# KittyEarsV2.net
KiCad netlist of a schematic drawn in EAGLE
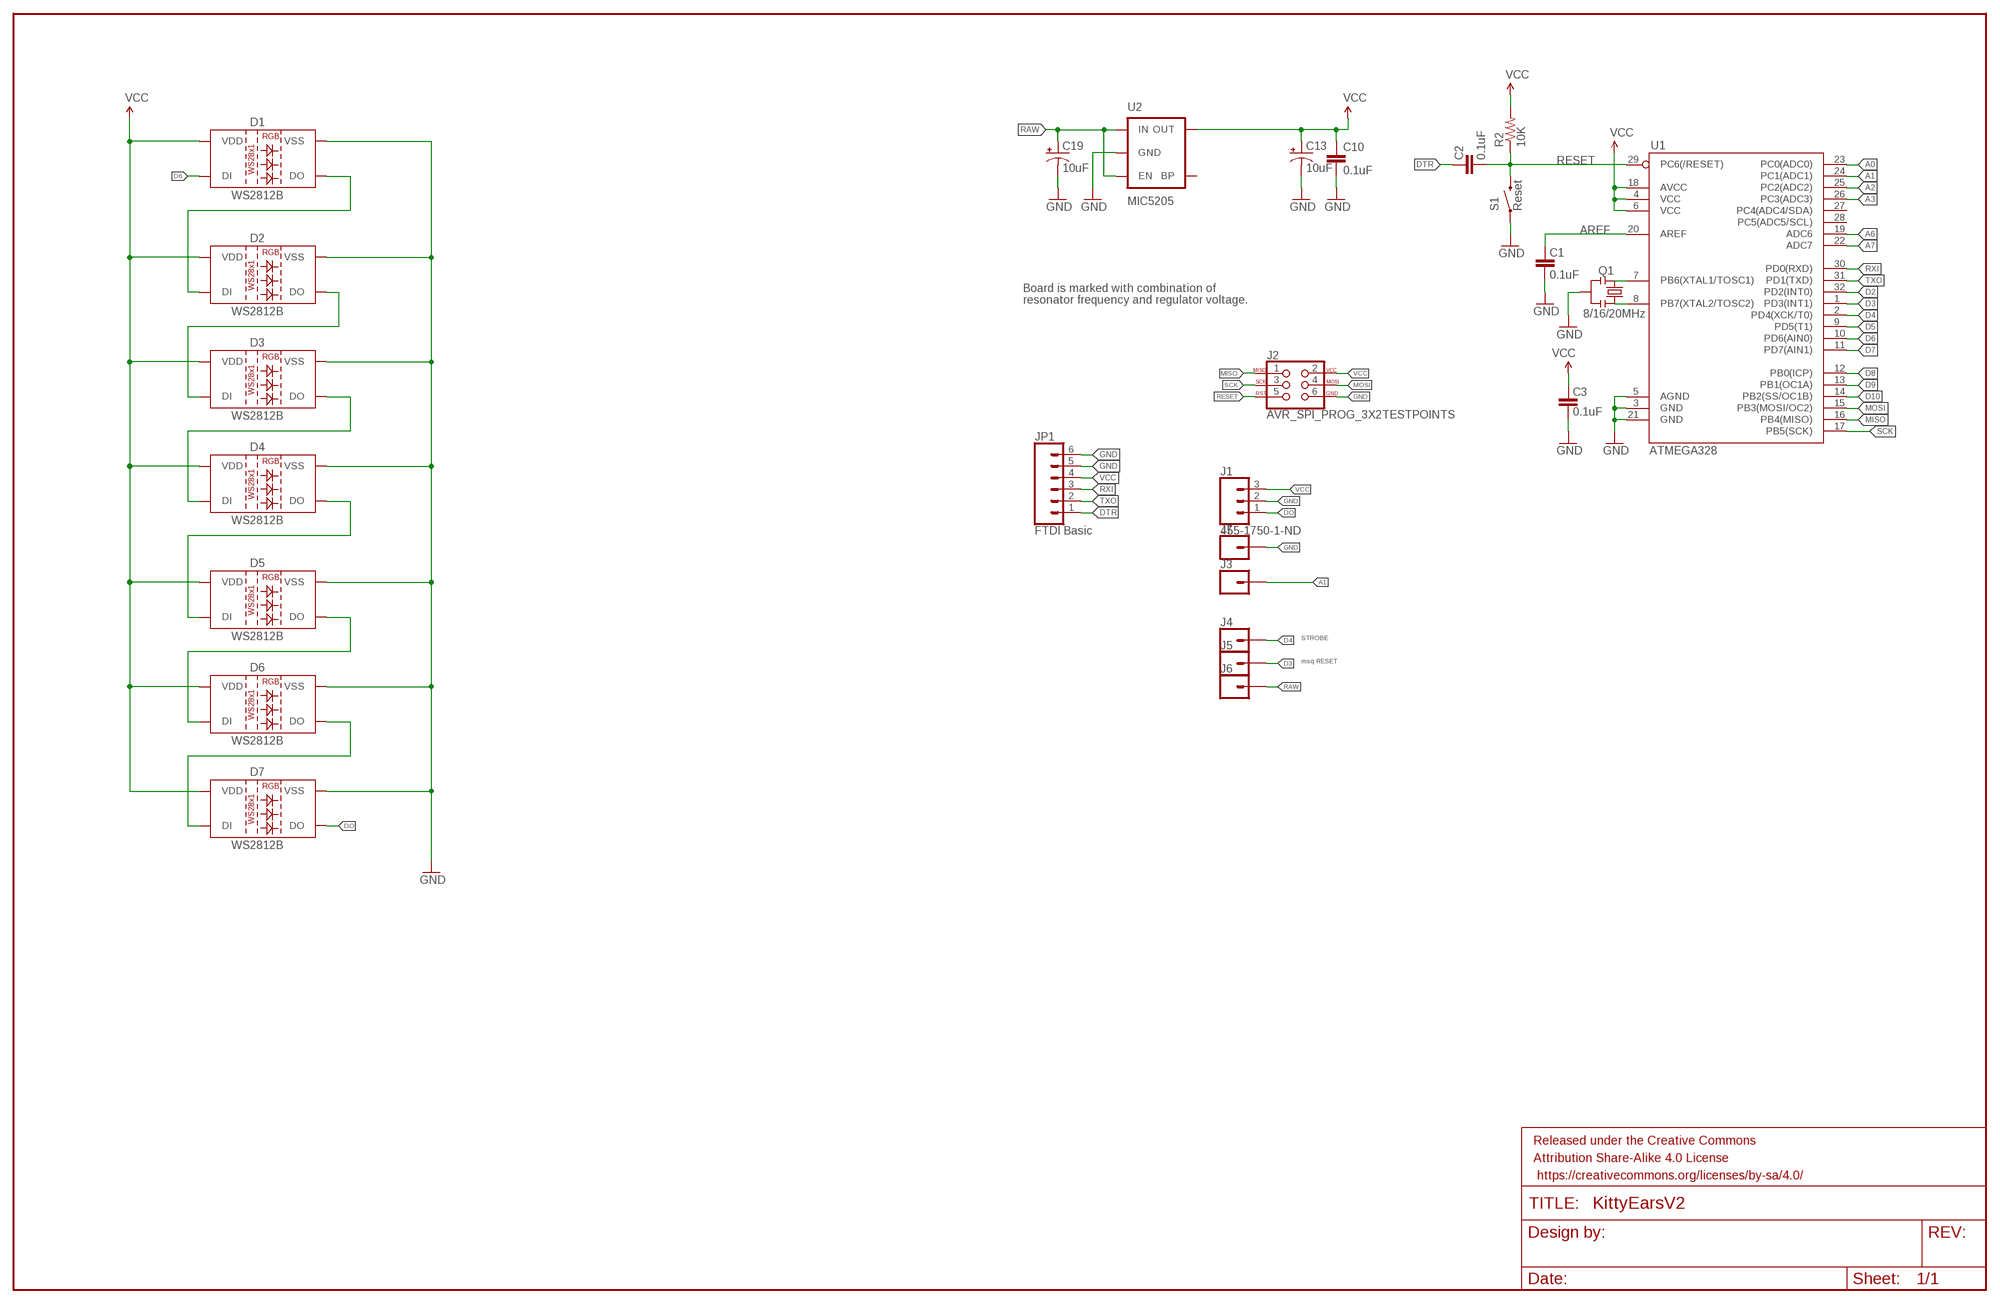
[diagram p0: schematic, sheet 1]

(export (version "E")
  (design (tool "Eeschema 10.0.6"))
  (components
    (comp (ref "C1")
      (value "0.1uF")
      (footprint "eagle-import:0603-CAP")
      (libsource (lib "eagle-import") (part "CAP0603-CAP"))
    )
    (comp (ref "C2")
      (value "0.1uF")
      (footprint "eagle-import:0603-CAP")
      (libsource (lib "eagle-import") (part "CAP0603-CAP"))
    )
    (comp (ref "C3")
      (value "0.1uF")
      (footprint "eagle-import:0603-CAP")
      (libsource (lib "eagle-import") (part "CAP0603-CAP"))
    )
    (comp (ref "C10")
      (value "0.1uF")
      (footprint "eagle-import:0603-CAP")
      (libsource (lib "eagle-import") (part "CAP0603-CAP"))
    )
    (comp (ref "C13")
      (value "10uF")
      (footprint "eagle-import:EIA3216")
      (libsource (lib "eagle-import") (part "CAP_POL1206"))
    )
    (comp (ref "C19")
      (value "10uF")
      (footprint "eagle-import:EIA3216")
      (libsource (lib "eagle-import") (part "CAP_POL1206"))
    )
    (comp (ref "D1")
      (value "WS2812B")
      (footprint "eagle-import:WS2812B")
      (libsource (lib "eagle-import") (part "WS2812B"))
    )
    (comp (ref "D2")
      (value "WS2812B")
      (footprint "eagle-import:WS2812B")
      (libsource (lib "eagle-import") (part "WS2812B"))
    )
    (comp (ref "D3")
      (value "WS2812B")
      (footprint "eagle-import:WS2812B")
      (libsource (lib "eagle-import") (part "WS2812B"))
    )
    (comp (ref "D4")
      (value "WS2812B")
      (footprint "eagle-import:WS2812B")
      (libsource (lib "eagle-import") (part "WS2812B"))
    )
    (comp (ref "D5")
      (value "WS2812B")
      (footprint "eagle-import:WS2812B")
      (libsource (lib "eagle-import") (part "WS2812B"))
    )
    (comp (ref "D6")
      (value "WS2812B")
      (footprint "eagle-import:WS2812B")
      (libsource (lib "eagle-import") (part "WS2812B"))
    )
    (comp (ref "D7")
      (value "WS2812B")
      (footprint "eagle-import:WS2812B")
      (libsource (lib "eagle-import") (part "WS2812B"))
    )
    (comp (ref "FRAME1")
      (value "FRAME-LEDGER")
      (footprint "eagle-import:CREATIVE_COMMONS")
      (libsource (lib "eagle-import") (part "FRAME-LEDGER"))
    )
    (comp (ref "J1")
      (value "455-1750-1-ND")
      (footprint "eagle-import:1X03")
      (libsource (lib "eagle-import") (part "CONN_03"))
    )
    (comp (ref "J2")
      (value "AVR_SPI_PROG_3X2TESTPOINTS")
      (footprint "eagle-import:2X3_TEST_POINTS")
      (libsource (lib "eagle-import") (part "AVR_SPI_PROG_3X2TESTPOINTS"))
    )
    (comp (ref "J3")
      (value "CONN_01")
      (footprint "eagle-import:1X01")
      (libsource (lib "eagle-import") (part "CONN_01"))
    )
    (comp (ref "J4")
      (value "CONN_01")
      (footprint "eagle-import:1X01")
      (libsource (lib "eagle-import") (part "CONN_01"))
    )
    (comp (ref "J5")
      (value "CONN_01")
      (footprint "eagle-import:1X01")
      (libsource (lib "eagle-import") (part "CONN_01"))
    )
    (comp (ref "J6")
      (value "CONN_01")
      (footprint "eagle-import:1X01")
      (libsource (lib "eagle-import") (part "CONN_01"))
    )
    (comp (ref "J7")
      (value "CONN_01")
      (footprint "eagle-import:1X01")
      (libsource (lib "eagle-import") (part "CONN_01"))
    )
    (comp (ref "JP1")
      (value "FTDI Basic")
      (footprint "eagle-import:1X06_SMD_STRAIGHT_COMBO")
      (libsource (lib "eagle-import") (part "CONN_06SMD-STRAIGHT-COMBO-FEMALE"))
    )
    (comp (ref "Q1")
      (value "8/16/20MHz")
      (footprint "eagle-import:RESONATOR-SMD-1_1")
      (libsource (lib "eagle-import") (part "RESONATOR1{colon}1"))
    )
    (comp (ref "R2")
      (value "10K")
      (footprint "eagle-import:0603-RES")
      (libsource (lib "eagle-import") (part "RESISTOR0603-RES"))
    )
    (comp (ref "S1")
      (value "Reset")
      (footprint "eagle-import:TACTILE-SWITCH-SMD-ALT01")
      (libsource (lib "eagle-import") (part "SWITCH-MOMENTARY-2SMD-ALT01"))
    )
    (comp (ref "U1")
      (value "ATMEGA328")
      (footprint "eagle-import:TQFP32-08")
      (libsource (lib "eagle-import") (part "ATMEGA168"))
    )
    (comp (ref "U2")
      (value "MIC5205")
      (footprint "eagle-import:SOT23-5")
      (libsource (lib "eagle-import") (part "V_REG_LDOSMD"))
    )
  )
  (nets
    (net (code "1") (name "/AREF") (class "Default")
      (node (ref "C1") (pin "2") (pinfunction "2_2") (pintype "passive"))
      (node (ref "U1") (pin "20") (pinfunction "AREF_20") (pintype "bidirectional"))
    )
    (net (code "2") (name "A0") (class "Default")
      (node (ref "U1") (pin "23") (pinfunction "PC0(ADC0)_23") (pintype "bidirectional"))
    )
    (net (code "3") (name "A1") (class "Default")
      (node (ref "J3") (pin "1") (pinfunction "1_1") (pintype "passive"))
      (node (ref "U1") (pin "24") (pinfunction "PC1(ADC1)_24") (pintype "bidirectional"))
    )
    (net (code "4") (name "A2") (class "Default")
      (node (ref "U1") (pin "25") (pinfunction "PC2(ADC2)_25") (pintype "bidirectional"))
    )
    (net (code "5") (name "A3") (class "Default")
      (node (ref "U1") (pin "26") (pinfunction "PC3(ADC3)_26") (pintype "bidirectional"))
    )
    (net (code "6") (name "A6") (class "Default")
      (node (ref "U1") (pin "19") (pinfunction "ADC6_19") (pintype "bidirectional"))
    )
    (net (code "7") (name "A7") (class "Default")
      (node (ref "U1") (pin "22") (pinfunction "ADC7_22") (pintype "bidirectional"))
    )
    (net (code "8") (name "D2") (class "Default")
      (node (ref "U1") (pin "32") (pinfunction "PD2(INT0)_32") (pintype "bidirectional"))
    )
    (net (code "9") (name "D3") (class "Default")
      (node (ref "J5") (pin "1") (pinfunction "1_1") (pintype "passive"))
      (node (ref "U1") (pin "1") (pinfunction "PD3(INT1)_1") (pintype "bidirectional"))
    )
    (net (code "10") (name "D4") (class "Default")
      (node (ref "J4") (pin "1") (pinfunction "1_1") (pintype "passive"))
      (node (ref "U1") (pin "2") (pinfunction "PD4(XCK/T0)_2") (pintype "bidirectional"))
    )
    (net (code "11") (name "D5") (class "Default")
      (node (ref "U1") (pin "9") (pinfunction "PD5(T1)_9") (pintype "bidirectional"))
    )
    (net (code "12") (name "D6") (class "Default")
      (node (ref "D1") (pin "4") (pinfunction "DI_4") (pintype "bidirectional"))
      (node (ref "U1") (pin "10") (pinfunction "PD6(AIN0)_10") (pintype "bidirectional"))
    )
    (net (code "13") (name "D7") (class "Default")
      (node (ref "U1") (pin "11") (pinfunction "PD7(AIN1)_11") (pintype "bidirectional"))
    )
    (net (code "14") (name "D8") (class "Default")
      (node (ref "U1") (pin "12") (pinfunction "PB0(ICP)_12") (pintype "bidirectional"))
    )
    (net (code "15") (name "D9") (class "Default")
      (node (ref "U1") (pin "13") (pinfunction "PB1(OC1A)_13") (pintype "bidirectional"))
    )
    (net (code "16") (name "D10") (class "Default")
      (node (ref "U1") (pin "14") (pinfunction "PB2(SS/OC1B)_14") (pintype "bidirectional"))
    )
    (net (code "17") (name "DO") (class "Default")
      (node (ref "D7") (pin "2") (pinfunction "DO_2") (pintype "bidirectional"))
      (node (ref "J1") (pin "1") (pinfunction "1_1") (pintype "passive"))
    )
    (net (code "18") (name "DTR") (class "Default")
      (node (ref "C2") (pin "2") (pinfunction "2_2") (pintype "passive"))
      (node (ref "JP1") (pin "1") (pinfunction "1_1") (pintype "passive"))
    )
    (net (code "19") (name "GND") (class "Default")
      (node (ref "C1") (pin "1") (pinfunction "1_1") (pintype "passive"))
      (node (ref "C10") (pin "2") (pinfunction "2_2") (pintype "passive"))
      (node (ref "C13") (pin "C") (pinfunction "-_C") (pintype "passive"))
      (node (ref "C19") (pin "C") (pinfunction "-_C") (pintype "passive"))
      (node (ref "C3") (pin "1") (pinfunction "1_1") (pintype "passive"))
      (node (ref "D1") (pin "3") (pinfunction "VSS_3") (pintype "bidirectional"))
      (node (ref "D2") (pin "3") (pinfunction "VSS_3") (pintype "bidirectional"))
      (node (ref "D3") (pin "3") (pinfunction "VSS_3") (pintype "bidirectional"))
      (node (ref "D4") (pin "3") (pinfunction "VSS_3") (pintype "bidirectional"))
      (node (ref "D5") (pin "3") (pinfunction "VSS_3") (pintype "bidirectional"))
      (node (ref "D6") (pin "3") (pinfunction "VSS_3") (pintype "bidirectional"))
      (node (ref "D7") (pin "3") (pinfunction "VSS_3") (pintype "bidirectional"))
      (node (ref "J1") (pin "2") (pinfunction "2_2") (pintype "passive"))
      (node (ref "J2") (pin "6") (pinfunction "6_6") (pintype "passive"))
      (node (ref "J7") (pin "1") (pinfunction "1_1") (pintype "passive"))
      (node (ref "JP1") (pin "5") (pinfunction "5_5") (pintype "passive"))
      (node (ref "JP1") (pin "6") (pinfunction "6_6") (pintype "passive"))
      (node (ref "Q1") (pin "2") (pinfunction "2_2") (pintype "passive"))
      (node (ref "S1") (pin "1") (pinfunction "1_1") (pintype "passive"))
      (node (ref "S1") (pin "2") (pinfunction "1_2") (pintype "passive"))
      (node (ref "U1") (pin "21") (pinfunction "GND_21") (pintype "bidirectional"))
      (node (ref "U1") (pin "3") (pinfunction "GND_3") (pintype "bidirectional"))
      (node (ref "U1") (pin "5") (pinfunction "AGND_5") (pintype "bidirectional"))
      (node (ref "U2") (pin "2") (pinfunction "GND_2") (pintype "input"))
    )
    (net (code "20") (name "MISO") (class "Default")
      (node (ref "J2") (pin "1") (pinfunction "1_1") (pintype "passive"))
      (node (ref "U1") (pin "16") (pinfunction "PB4(MISO)_16") (pintype "bidirectional"))
    )
    (net (code "21") (name "MOSI") (class "Default")
      (node (ref "J2") (pin "4") (pinfunction "4_4") (pintype "passive"))
      (node (ref "U1") (pin "15") (pinfunction "PB3(MOSI/OC2)_15") (pintype "bidirectional"))
    )
    (net (code "22") (name "Net-(D1-DO)") (class "Default")
      (node (ref "D1") (pin "2") (pinfunction "DO_2") (pintype "bidirectional"))
      (node (ref "D2") (pin "4") (pinfunction "DI_4") (pintype "bidirectional"))
    )
    (net (code "23") (name "Net-(D2-DO)") (class "Default")
      (node (ref "D2") (pin "2") (pinfunction "DO_2") (pintype "bidirectional"))
      (node (ref "D3") (pin "4") (pinfunction "DI_4") (pintype "bidirectional"))
    )
    (net (code "24") (name "Net-(D3-DO)") (class "Default")
      (node (ref "D3") (pin "2") (pinfunction "DO_2") (pintype "bidirectional"))
      (node (ref "D4") (pin "4") (pinfunction "DI_4") (pintype "bidirectional"))
    )
    (net (code "25") (name "Net-(D4-DO)") (class "Default")
      (node (ref "D4") (pin "2") (pinfunction "DO_2") (pintype "bidirectional"))
      (node (ref "D5") (pin "4") (pinfunction "DI_4") (pintype "bidirectional"))
    )
    (net (code "26") (name "Net-(D5-DO)") (class "Default")
      (node (ref "D5") (pin "2") (pinfunction "DO_2") (pintype "bidirectional"))
      (node (ref "D6") (pin "4") (pinfunction "DI_4") (pintype "bidirectional"))
    )
    (net (code "27") (name "Net-(D6-DO)") (class "Default")
      (node (ref "D6") (pin "2") (pinfunction "DO_2") (pintype "bidirectional"))
      (node (ref "D7") (pin "4") (pinfunction "DI_4") (pintype "bidirectional"))
    )
    (net (code "28") (name "Net-(U1-PB6(XTAL1{slash}TOSC1))") (class "Default")
      (node (ref "Q1") (pin "1") (pinfunction "1_1") (pintype "passive"))
      (node (ref "U1") (pin "7") (pinfunction "PB6(XTAL1/TOSC1)_7") (pintype "bidirectional"))
    )
    (net (code "29") (name "Net-(U1-PB7(XTAL2{slash}TOSC2))") (class "Default")
      (node (ref "Q1") (pin "3") (pinfunction "3_3") (pintype "passive"))
      (node (ref "U1") (pin "8") (pinfunction "PB7(XTAL2/TOSC2)_8") (pintype "bidirectional"))
    )
    (net (code "30") (name "RAW") (class "Default")
      (node (ref "C19") (pin "A") (pinfunction "+_A") (pintype "passive"))
      (node (ref "J6") (pin "1") (pinfunction "1_1") (pintype "passive"))
      (node (ref "U2") (pin "1") (pinfunction "IN_1") (pintype "input"))
      (node (ref "U2") (pin "3") (pinfunction "EN_3") (pintype "input"))
    )
    (net (code "31") (name "RESET") (class "Default")
      (node (ref "C2") (pin "1") (pinfunction "1_1") (pintype "passive"))
      (node (ref "J2") (pin "5") (pinfunction "5_5") (pintype "passive"))
      (node (ref "R2") (pin "1") (pinfunction "1_1") (pintype "passive"))
      (node (ref "S1") (pin "3") (pinfunction "2_3") (pintype "passive"))
      (node (ref "S1") (pin "4") (pinfunction "2_4") (pintype "passive"))
      (node (ref "U1") (pin "29") (pinfunction "PC6(/RESET)_29") (pintype "bidirectional"))
    )
    (net (code "32") (name "RXI") (class "Default")
      (node (ref "JP1") (pin "3") (pinfunction "3_3") (pintype "passive"))
      (node (ref "U1") (pin "30") (pinfunction "PD0(RXD)_30") (pintype "bidirectional"))
    )
    (net (code "33") (name "SCK") (class "Default")
      (node (ref "J2") (pin "3") (pinfunction "3_3") (pintype "passive"))
      (node (ref "U1") (pin "17") (pinfunction "PB5(SCK)_17") (pintype "bidirectional"))
    )
    (net (code "34") (name "TXO") (class "Default")
      (node (ref "JP1") (pin "2") (pinfunction "2_2") (pintype "passive"))
      (node (ref "U1") (pin "31") (pinfunction "PD1(TXD)_31") (pintype "bidirectional"))
    )
    (net (code "35") (name "VCC") (class "Default")
      (node (ref "C10") (pin "1") (pinfunction "1_1") (pintype "passive"))
      (node (ref "C13") (pin "A") (pinfunction "+_A") (pintype "passive"))
      (node (ref "C3") (pin "2") (pinfunction "2_2") (pintype "passive"))
      (node (ref "D1") (pin "1") (pinfunction "VDD_1") (pintype "bidirectional"))
      (node (ref "D2") (pin "1") (pinfunction "VDD_1") (pintype "bidirectional"))
      (node (ref "D3") (pin "1") (pinfunction "VDD_1") (pintype "bidirectional"))
      (node (ref "D4") (pin "1") (pinfunction "VDD_1") (pintype "bidirectional"))
      (node (ref "D5") (pin "1") (pinfunction "VDD_1") (pintype "bidirectional"))
      (node (ref "D6") (pin "1") (pinfunction "VDD_1") (pintype "bidirectional"))
      (node (ref "D7") (pin "1") (pinfunction "VDD_1") (pintype "bidirectional"))
      (node (ref "J1") (pin "3") (pinfunction "3_3") (pintype "passive"))
      (node (ref "J2") (pin "2") (pinfunction "2_2") (pintype "passive"))
      (node (ref "JP1") (pin "4") (pinfunction "4_4") (pintype "passive"))
      (node (ref "R2") (pin "2") (pinfunction "2_2") (pintype "passive"))
      (node (ref "U1") (pin "18") (pinfunction "AVCC_18") (pintype "bidirectional"))
      (node (ref "U1") (pin "4") (pinfunction "VCC_4") (pintype "bidirectional"))
      (node (ref "U1") (pin "6") (pinfunction "VCC_6") (pintype "bidirectional"))
      (node (ref "U2") (pin "5") (pinfunction "OUT_5") (pintype "passive"))
    )
    (net (code "36") (name "unconnected-(U1-PC4(ADC4{slash}SDA)-Pad27)") (class "Default")
      (node (ref "U1") (pin "27") (pinfunction "PC4(ADC4/SDA)_27") (pintype "bidirectional"))
    )
    (net (code "37") (name "unconnected-(U1-PC5(ADC5{slash}SCL)-Pad28)") (class "Default")
      (node (ref "U1") (pin "28") (pinfunction "PC5(ADC5/SCL)_28") (pintype "bidirectional"))
    )
    (net (code "38") (name "unconnected-(U2-BP-Pad4)") (class "Default")
      (node (ref "U2") (pin "4") (pinfunction "BP_4") (pintype "input"))
    )
  )
)
